# Raspberry_LCD_2023-10-31_10-21-50.net
KiCad netlist of a schematic drawn in EasyEDA Pro
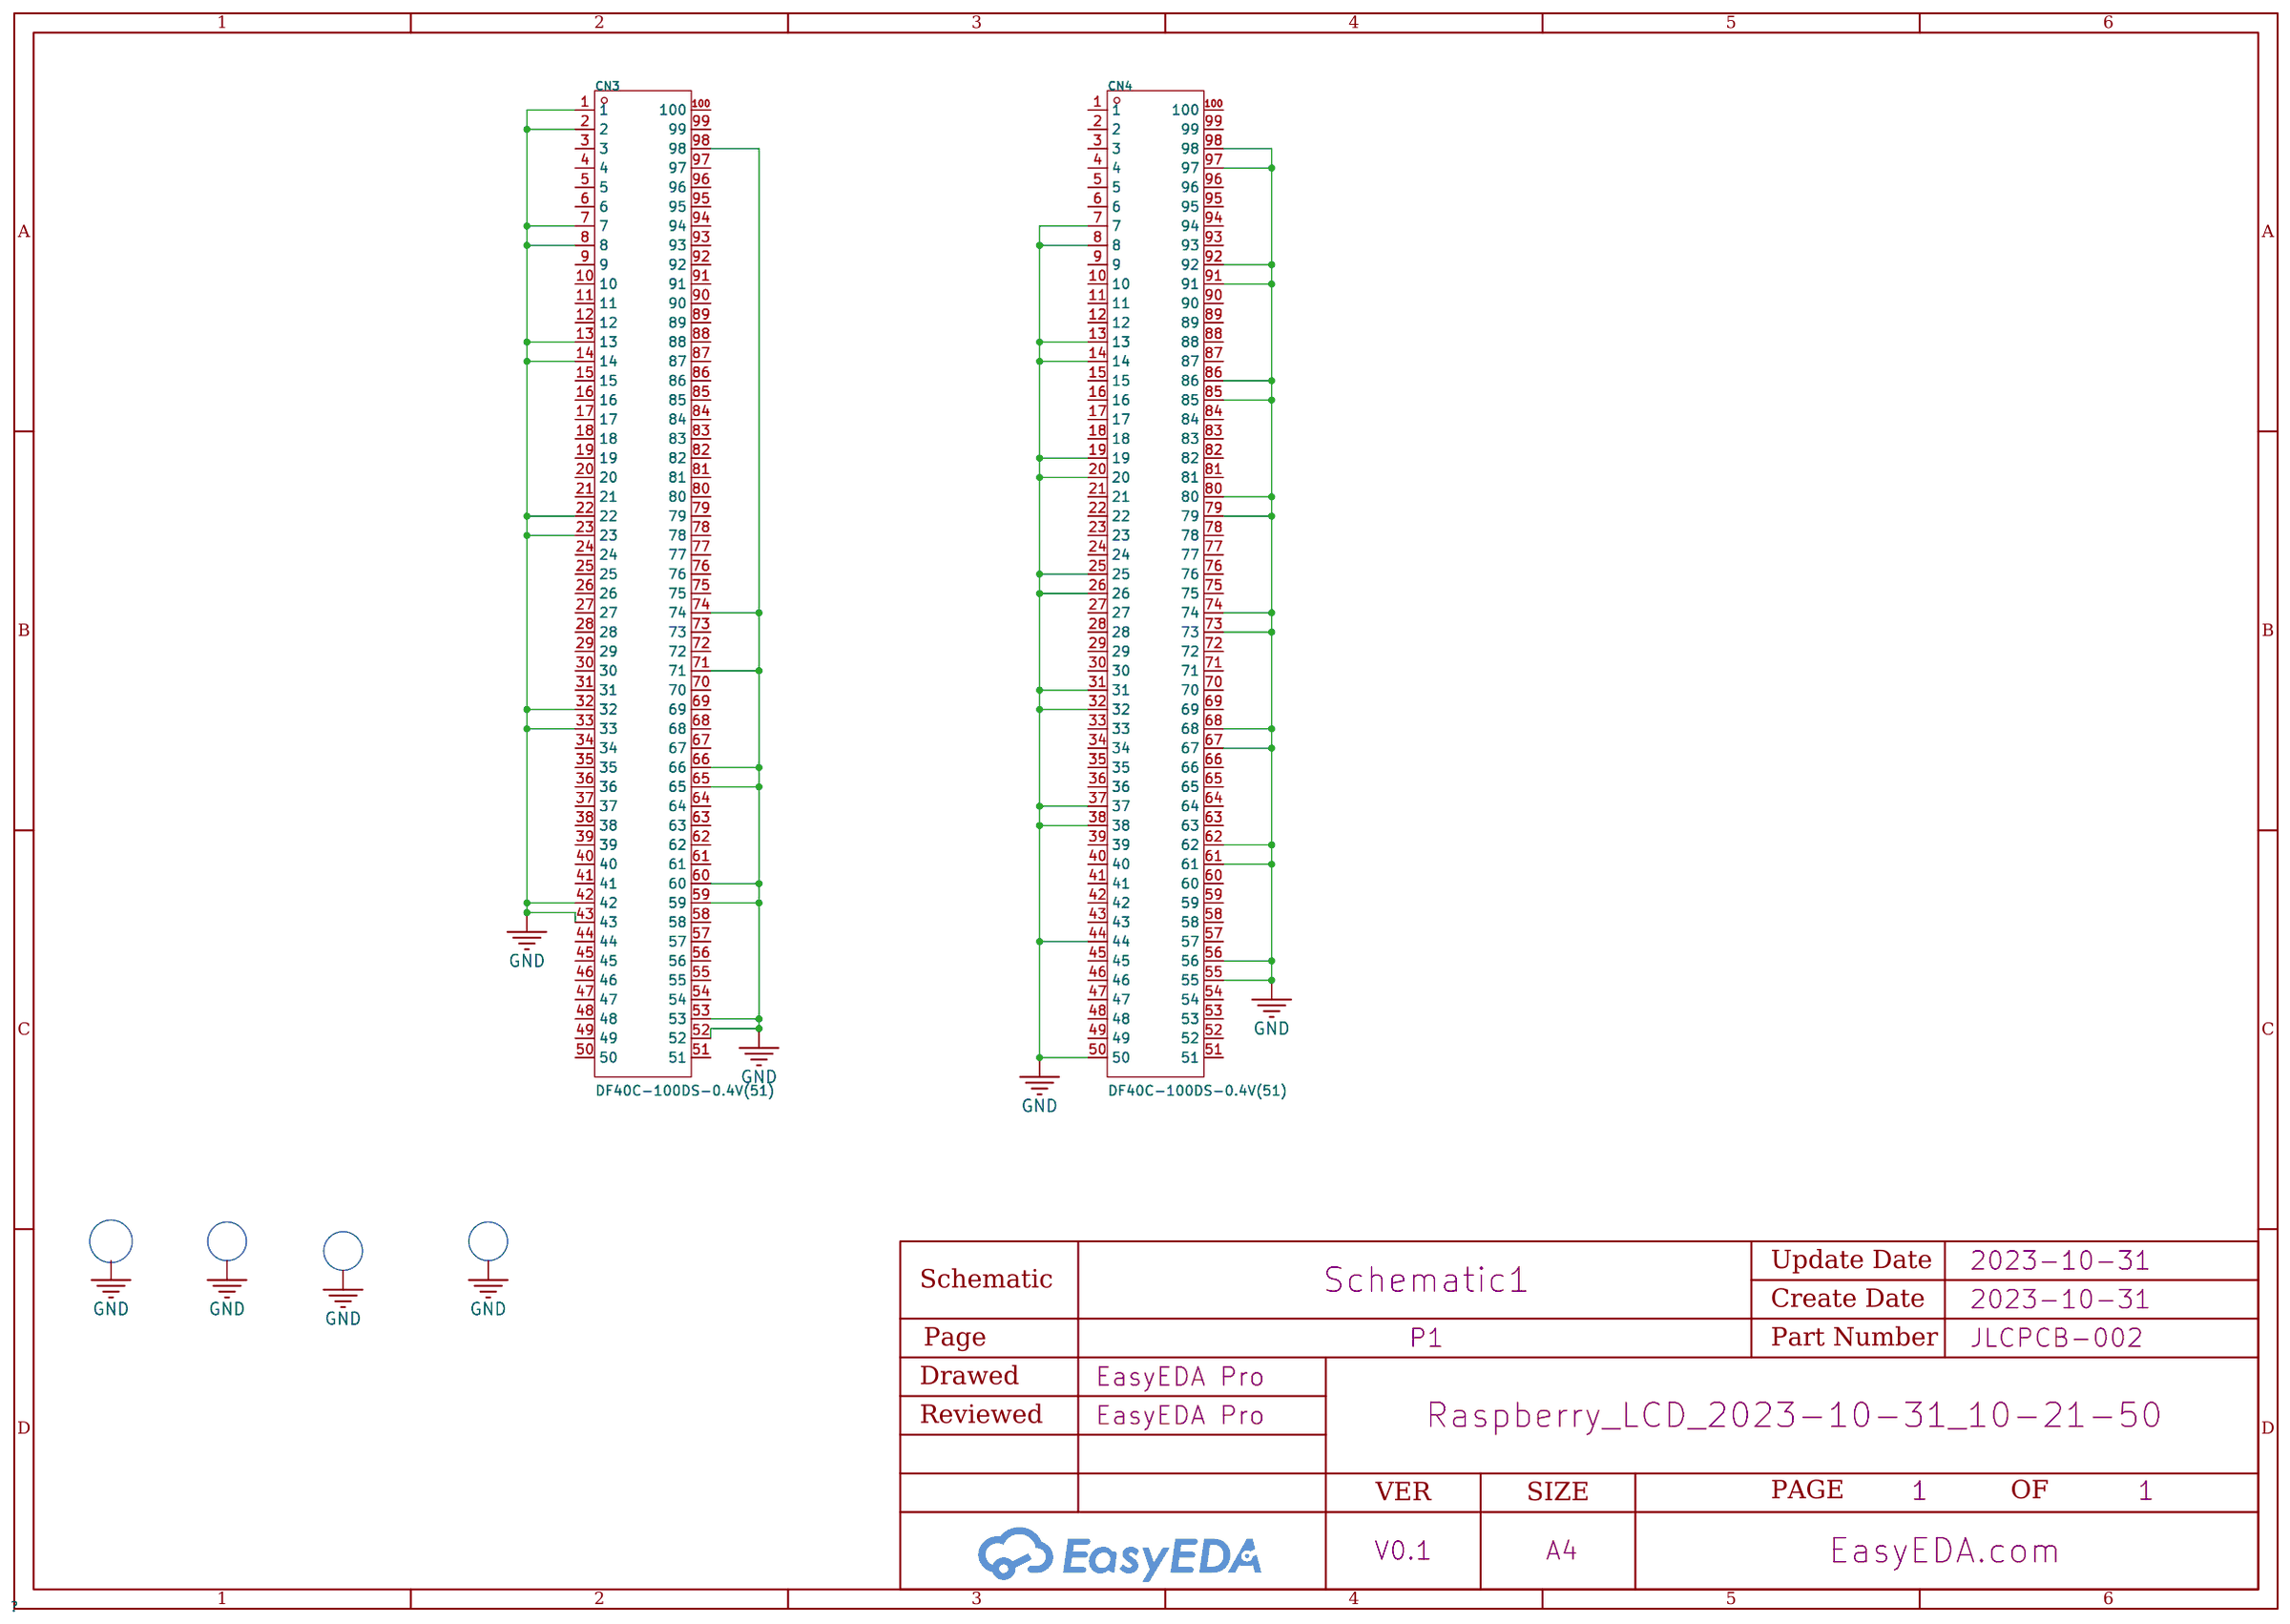
[diagram p0: schematic sheet]

(export (version "E")
  (design (tool "Eeschema 10.0.6"))
  (components
    (comp (ref "CN3")
      (value "DF40C-100DS-0.4V(51)")
      (footprint "easyedapro:CONN-SMD_DF40C-100DS-0.4V-51")
      (fields (field (name "Manufacturer") "HRS(广濑)"))
      (libsource (lib "easyedapro") (part "DF40C-100DS-0.4V(51)"))
    )
    (comp (ref "CN4")
      (value "DF40C-100DS-0.4V(51)")
      (footprint "easyedapro:CONN-SMD_DF40C-100DS-0.4V-51")
      (fields (field (name "Manufacturer") "HRS(广濑)"))
      (libsource (lib "easyedapro") (part "DF40C-100DS-0.4V(51)"))
    )
  )
  (nets
    (net (code "1") (name "GND") (class "Default")
      (node (ref "CN3") (pin "1") (pinfunction "1_1") (pintype "input"))
      (node (ref "CN3") (pin "13") (pinfunction "13_13") (pintype "input"))
      (node (ref "CN3") (pin "14") (pinfunction "14_14") (pintype "input"))
      (node (ref "CN3") (pin "2") (pinfunction "2_2") (pintype "input"))
      (node (ref "CN3") (pin "22") (pinfunction "22_22") (pintype "input"))
      (node (ref "CN3") (pin "23") (pinfunction "23_23") (pintype "input"))
      (node (ref "CN3") (pin "32") (pinfunction "32_32") (pintype "input"))
      (node (ref "CN3") (pin "33") (pinfunction "33_33") (pintype "input"))
      (node (ref "CN3") (pin "42") (pinfunction "42_42") (pintype "input"))
      (node (ref "CN3") (pin "43") (pinfunction "43_43") (pintype "input"))
      (node (ref "CN3") (pin "52") (pinfunction "52_52") (pintype "input"))
      (node (ref "CN3") (pin "53") (pinfunction "53_53") (pintype "input"))
      (node (ref "CN3") (pin "59") (pinfunction "59_59") (pintype "input"))
      (node (ref "CN3") (pin "60") (pinfunction "60_60") (pintype "input"))
      (node (ref "CN3") (pin "65") (pinfunction "65_65") (pintype "input"))
      (node (ref "CN3") (pin "66") (pinfunction "66_66") (pintype "input"))
      (node (ref "CN3") (pin "7") (pinfunction "7_7") (pintype "input"))
      (node (ref "CN3") (pin "71") (pinfunction "71_71") (pintype "input"))
      (node (ref "CN3") (pin "74") (pinfunction "74_74") (pintype "input"))
      (node (ref "CN3") (pin "8") (pinfunction "8_8") (pintype "input"))
      (node (ref "CN3") (pin "98") (pinfunction "98_98") (pintype "input"))
      (node (ref "CN4") (pin "13") (pinfunction "13_13") (pintype "input"))
      (node (ref "CN4") (pin "14") (pinfunction "14_14") (pintype "input"))
      (node (ref "CN4") (pin "19") (pinfunction "19_19") (pintype "input"))
      (node (ref "CN4") (pin "20") (pinfunction "20_20") (pintype "input"))
      (node (ref "CN4") (pin "25") (pinfunction "25_25") (pintype "input"))
      (node (ref "CN4") (pin "26") (pinfunction "26_26") (pintype "input"))
      (node (ref "CN4") (pin "31") (pinfunction "31_31") (pintype "input"))
      (node (ref "CN4") (pin "32") (pinfunction "32_32") (pintype "input"))
      (node (ref "CN4") (pin "37") (pinfunction "37_37") (pintype "input"))
      (node (ref "CN4") (pin "38") (pinfunction "38_38") (pintype "input"))
      (node (ref "CN4") (pin "44") (pinfunction "44_44") (pintype "input"))
      (node (ref "CN4") (pin "50") (pinfunction "50_50") (pintype "input"))
      (node (ref "CN4") (pin "55") (pinfunction "55_55") (pintype "input"))
      (node (ref "CN4") (pin "56") (pinfunction "56_56") (pintype "input"))
      (node (ref "CN4") (pin "61") (pinfunction "61_61") (pintype "input"))
      (node (ref "CN4") (pin "62") (pinfunction "62_62") (pintype "input"))
      (node (ref "CN4") (pin "67") (pinfunction "67_67") (pintype "input"))
      (node (ref "CN4") (pin "68") (pinfunction "68_68") (pintype "input"))
      (node (ref "CN4") (pin "7") (pinfunction "7_7") (pintype "input"))
      (node (ref "CN4") (pin "73") (pinfunction "73_73") (pintype "input"))
      (node (ref "CN4") (pin "74") (pinfunction "74_74") (pintype "input"))
      (node (ref "CN4") (pin "79") (pinfunction "79_79") (pintype "input"))
      (node (ref "CN4") (pin "8") (pinfunction "8_8") (pintype "input"))
      (node (ref "CN4") (pin "80") (pinfunction "80_80") (pintype "input"))
      (node (ref "CN4") (pin "85") (pinfunction "85_85") (pintype "input"))
      (node (ref "CN4") (pin "86") (pinfunction "86_86") (pintype "input"))
      (node (ref "CN4") (pin "91") (pinfunction "91_91") (pintype "input"))
      (node (ref "CN4") (pin "92") (pinfunction "92_92") (pintype "input"))
      (node (ref "CN4") (pin "97") (pinfunction "97_97") (pintype "input"))
      (node (ref "CN4") (pin "98") (pinfunction "98_98") (pintype "input"))
    )
    (net (code "2") (name "unconnected-(CN3-Pad3)") (class "Default")
      (node (ref "CN3") (pin "3") (pinfunction "3_3") (pintype "input"))
    )
    (net (code "3") (name "unconnected-(CN3-Pad4)") (class "Default")
      (node (ref "CN3") (pin "4") (pinfunction "4_4") (pintype "input"))
    )
    (net (code "4") (name "unconnected-(CN3-Pad5)") (class "Default")
      (node (ref "CN3") (pin "5") (pinfunction "5_5") (pintype "input"))
    )
    (net (code "5") (name "unconnected-(CN3-Pad6)") (class "Default")
      (node (ref "CN3") (pin "6") (pinfunction "6_6") (pintype "input"))
    )
    (net (code "6") (name "unconnected-(CN3-Pad9)") (class "Default")
      (node (ref "CN3") (pin "9") (pinfunction "9_9") (pintype "input"))
    )
    (net (code "7") (name "unconnected-(CN3-Pad10)") (class "Default")
      (node (ref "CN3") (pin "10") (pinfunction "10_10") (pintype "input"))
    )
    (net (code "8") (name "unconnected-(CN3-Pad11)") (class "Default")
      (node (ref "CN3") (pin "11") (pinfunction "11_11") (pintype "input"))
    )
    (net (code "9") (name "unconnected-(CN3-Pad12)") (class "Default")
      (node (ref "CN3") (pin "12") (pinfunction "12_12") (pintype "input"))
    )
    (net (code "10") (name "unconnected-(CN3-Pad15)") (class "Default")
      (node (ref "CN3") (pin "15") (pinfunction "15_15") (pintype "input"))
    )
    (net (code "11") (name "unconnected-(CN3-Pad16)") (class "Default")
      (node (ref "CN3") (pin "16") (pinfunction "16_16") (pintype "input"))
    )
    (net (code "12") (name "unconnected-(CN3-Pad17)") (class "Default")
      (node (ref "CN3") (pin "17") (pinfunction "17_17") (pintype "input"))
    )
    (net (code "13") (name "unconnected-(CN3-Pad18)") (class "Default")
      (node (ref "CN3") (pin "18") (pinfunction "18_18") (pintype "input"))
    )
    (net (code "14") (name "unconnected-(CN3-Pad19)") (class "Default")
      (node (ref "CN3") (pin "19") (pinfunction "19_19") (pintype "input"))
    )
    (net (code "15") (name "unconnected-(CN3-Pad20)") (class "Default")
      (node (ref "CN3") (pin "20") (pinfunction "20_20") (pintype "input"))
    )
    (net (code "16") (name "unconnected-(CN3-Pad21)") (class "Default")
      (node (ref "CN3") (pin "21") (pinfunction "21_21") (pintype "input"))
    )
    (net (code "17") (name "unconnected-(CN3-Pad24)") (class "Default")
      (node (ref "CN3") (pin "24") (pinfunction "24_24") (pintype "input"))
    )
    (net (code "18") (name "unconnected-(CN3-Pad25)") (class "Default")
      (node (ref "CN3") (pin "25") (pinfunction "25_25") (pintype "input"))
    )
    (net (code "19") (name "unconnected-(CN3-Pad26)") (class "Default")
      (node (ref "CN3") (pin "26") (pinfunction "26_26") (pintype "input"))
    )
    (net (code "20") (name "unconnected-(CN3-Pad27)") (class "Default")
      (node (ref "CN3") (pin "27") (pinfunction "27_27") (pintype "input"))
    )
    (net (code "21") (name "unconnected-(CN3-Pad28)") (class "Default")
      (node (ref "CN3") (pin "28") (pinfunction "28_28") (pintype "input"))
    )
    (net (code "22") (name "unconnected-(CN3-Pad29)") (class "Default")
      (node (ref "CN3") (pin "29") (pinfunction "29_29") (pintype "input"))
    )
    (net (code "23") (name "unconnected-(CN3-Pad30)") (class "Default")
      (node (ref "CN3") (pin "30") (pinfunction "30_30") (pintype "input"))
    )
    (net (code "24") (name "unconnected-(CN3-Pad31)") (class "Default")
      (node (ref "CN3") (pin "31") (pinfunction "31_31") (pintype "input"))
    )
    (net (code "25") (name "unconnected-(CN3-Pad34)") (class "Default")
      (node (ref "CN3") (pin "34") (pinfunction "34_34") (pintype "input"))
    )
    (net (code "26") (name "unconnected-(CN3-Pad35)") (class "Default")
      (node (ref "CN3") (pin "35") (pinfunction "35_35") (pintype "input"))
    )
    (net (code "27") (name "unconnected-(CN3-Pad36)") (class "Default")
      (node (ref "CN3") (pin "36") (pinfunction "36_36") (pintype "input"))
    )
    (net (code "28") (name "unconnected-(CN3-Pad37)") (class "Default")
      (node (ref "CN3") (pin "37") (pinfunction "37_37") (pintype "input"))
    )
    (net (code "29") (name "unconnected-(CN3-Pad38)") (class "Default")
      (node (ref "CN3") (pin "38") (pinfunction "38_38") (pintype "input"))
    )
    (net (code "30") (name "unconnected-(CN3-Pad39)") (class "Default")
      (node (ref "CN3") (pin "39") (pinfunction "39_39") (pintype "input"))
    )
    (net (code "31") (name "unconnected-(CN3-Pad40)") (class "Default")
      (node (ref "CN3") (pin "40") (pinfunction "40_40") (pintype "input"))
    )
    (net (code "32") (name "unconnected-(CN3-Pad41)") (class "Default")
      (node (ref "CN3") (pin "41") (pinfunction "41_41") (pintype "input"))
    )
    (net (code "33") (name "unconnected-(CN3-Pad44)") (class "Default")
      (node (ref "CN3") (pin "44") (pinfunction "44_44") (pintype "input"))
    )
    (net (code "34") (name "unconnected-(CN3-Pad45)") (class "Default")
      (node (ref "CN3") (pin "45") (pinfunction "45_45") (pintype "input"))
    )
    (net (code "35") (name "unconnected-(CN3-Pad46)") (class "Default")
      (node (ref "CN3") (pin "46") (pinfunction "46_46") (pintype "input"))
    )
    (net (code "36") (name "unconnected-(CN3-Pad47)") (class "Default")
      (node (ref "CN3") (pin "47") (pinfunction "47_47") (pintype "input"))
    )
    (net (code "37") (name "unconnected-(CN3-Pad48)") (class "Default")
      (node (ref "CN3") (pin "48") (pinfunction "48_48") (pintype "input"))
    )
    (net (code "38") (name "unconnected-(CN3-Pad49)") (class "Default")
      (node (ref "CN3") (pin "49") (pinfunction "49_49") (pintype "input"))
    )
    (net (code "39") (name "unconnected-(CN3-Pad50)") (class "Default")
      (node (ref "CN3") (pin "50") (pinfunction "50_50") (pintype "input"))
    )
    (net (code "40") (name "unconnected-(CN3-Pad51)") (class "Default")
      (node (ref "CN3") (pin "51") (pinfunction "51_51") (pintype "input"))
    )
    (net (code "41") (name "unconnected-(CN3-Pad54)") (class "Default")
      (node (ref "CN3") (pin "54") (pinfunction "54_54") (pintype "input"))
    )
    (net (code "42") (name "unconnected-(CN3-Pad55)") (class "Default")
      (node (ref "CN3") (pin "55") (pinfunction "55_55") (pintype "input"))
    )
    (net (code "43") (name "unconnected-(CN3-Pad56)") (class "Default")
      (node (ref "CN3") (pin "56") (pinfunction "56_56") (pintype "input"))
    )
    (net (code "44") (name "unconnected-(CN3-Pad57)") (class "Default")
      (node (ref "CN3") (pin "57") (pinfunction "57_57") (pintype "input"))
    )
    (net (code "45") (name "unconnected-(CN3-Pad58)") (class "Default")
      (node (ref "CN3") (pin "58") (pinfunction "58_58") (pintype "input"))
    )
    (net (code "46") (name "unconnected-(CN3-Pad61)") (class "Default")
      (node (ref "CN3") (pin "61") (pinfunction "61_61") (pintype "input"))
    )
    (net (code "47") (name "unconnected-(CN3-Pad62)") (class "Default")
      (node (ref "CN3") (pin "62") (pinfunction "62_62") (pintype "input"))
    )
    (net (code "48") (name "unconnected-(CN3-Pad63)") (class "Default")
      (node (ref "CN3") (pin "63") (pinfunction "63_63") (pintype "input"))
    )
    (net (code "49") (name "unconnected-(CN3-Pad64)") (class "Default")
      (node (ref "CN3") (pin "64") (pinfunction "64_64") (pintype "input"))
    )
    (net (code "50") (name "unconnected-(CN3-Pad67)") (class "Default")
      (node (ref "CN3") (pin "67") (pinfunction "67_67") (pintype "input"))
    )
    (net (code "51") (name "unconnected-(CN3-Pad68)") (class "Default")
      (node (ref "CN3") (pin "68") (pinfunction "68_68") (pintype "input"))
    )
    (net (code "52") (name "unconnected-(CN3-Pad69)") (class "Default")
      (node (ref "CN3") (pin "69") (pinfunction "69_69") (pintype "input"))
    )
    (net (code "53") (name "unconnected-(CN3-Pad70)") (class "Default")
      (node (ref "CN3") (pin "70") (pinfunction "70_70") (pintype "input"))
    )
    (net (code "54") (name "unconnected-(CN3-Pad72)") (class "Default")
      (node (ref "CN3") (pin "72") (pinfunction "72_72") (pintype "input"))
    )
    (net (code "55") (name "unconnected-(CN3-Pad73)") (class "Default")
      (node (ref "CN3") (pin "73") (pinfunction "73_73") (pintype "input"))
    )
    (net (code "56") (name "unconnected-(CN3-Pad75)") (class "Default")
      (node (ref "CN3") (pin "75") (pinfunction "75_75") (pintype "input"))
    )
    (net (code "57") (name "unconnected-(CN3-Pad76)") (class "Default")
      (node (ref "CN3") (pin "76") (pinfunction "76_76") (pintype "input"))
    )
    (net (code "58") (name "unconnected-(CN3-Pad77)") (class "Default")
      (node (ref "CN3") (pin "77") (pinfunction "77_77") (pintype "input"))
    )
    (net (code "59") (name "unconnected-(CN3-Pad78)") (class "Default")
      (node (ref "CN3") (pin "78") (pinfunction "78_78") (pintype "input"))
    )
    (net (code "60") (name "unconnected-(CN3-Pad79)") (class "Default")
      (node (ref "CN3") (pin "79") (pinfunction "79_79") (pintype "input"))
    )
    (net (code "61") (name "unconnected-(CN3-Pad80)") (class "Default")
      (node (ref "CN3") (pin "80") (pinfunction "80_80") (pintype "input"))
    )
    (net (code "62") (name "unconnected-(CN3-Pad81)") (class "Default")
      (node (ref "CN3") (pin "81") (pinfunction "81_81") (pintype "input"))
    )
    (net (code "63") (name "unconnected-(CN3-Pad82)") (class "Default")
      (node (ref "CN3") (pin "82") (pinfunction "82_82") (pintype "input"))
    )
    (net (code "64") (name "unconnected-(CN3-Pad83)") (class "Default")
      (node (ref "CN3") (pin "83") (pinfunction "83_83") (pintype "input"))
    )
    (net (code "65") (name "unconnected-(CN3-Pad84)") (class "Default")
      (node (ref "CN3") (pin "84") (pinfunction "84_84") (pintype "input"))
    )
    (net (code "66") (name "unconnected-(CN3-Pad85)") (class "Default")
      (node (ref "CN3") (pin "85") (pinfunction "85_85") (pintype "input"))
    )
    (net (code "67") (name "unconnected-(CN3-Pad86)") (class "Default")
      (node (ref "CN3") (pin "86") (pinfunction "86_86") (pintype "input"))
    )
    (net (code "68") (name "unconnected-(CN3-Pad87)") (class "Default")
      (node (ref "CN3") (pin "87") (pinfunction "87_87") (pintype "input"))
    )
    (net (code "69") (name "unconnected-(CN3-Pad88)") (class "Default")
      (node (ref "CN3") (pin "88") (pinfunction "88_88") (pintype "input"))
    )
    (net (code "70") (name "unconnected-(CN3-Pad89)") (class "Default")
      (node (ref "CN3") (pin "89") (pinfunction "89_89") (pintype "input"))
    )
    (net (code "71") (name "unconnected-(CN3-Pad90)") (class "Default")
      (node (ref "CN3") (pin "90") (pinfunction "90_90") (pintype "input"))
    )
    (net (code "72") (name "unconnected-(CN3-Pad91)") (class "Default")
      (node (ref "CN3") (pin "91") (pinfunction "91_91") (pintype "input"))
    )
    (net (code "73") (name "unconnected-(CN3-Pad92)") (class "Default")
      (node (ref "CN3") (pin "92") (pinfunction "92_92") (pintype "input"))
    )
    (net (code "74") (name "unconnected-(CN3-Pad93)") (class "Default")
      (node (ref "CN3") (pin "93") (pinfunction "93_93") (pintype "input"))
    )
    (net (code "75") (name "unconnected-(CN3-Pad94)") (class "Default")
      (node (ref "CN3") (pin "94") (pinfunction "94_94") (pintype "input"))
    )
    (net (code "76") (name "unconnected-(CN3-Pad95)") (class "Default")
      (node (ref "CN3") (pin "95") (pinfunction "95_95") (pintype "input"))
    )
    (net (code "77") (name "unconnected-(CN3-Pad96)") (class "Default")
      (node (ref "CN3") (pin "96") (pinfunction "96_96") (pintype "input"))
    )
    (net (code "78") (name "unconnected-(CN3-Pad97)") (class "Default")
      (node (ref "CN3") (pin "97") (pinfunction "97_97") (pintype "input"))
    )
    (net (code "79") (name "unconnected-(CN3-Pad99)") (class "Default")
      (node (ref "CN3") (pin "99") (pinfunction "99_99") (pintype "input"))
    )
    (net (code "80") (name "unconnected-(CN3-Pad100)") (class "Default")
      (node (ref "CN3") (pin "100") (pinfunction "100_100") (pintype "input"))
    )
    (net (code "81") (name "unconnected-(CN4-Pad1)") (class "Default")
      (node (ref "CN4") (pin "1") (pinfunction "1_1") (pintype "input"))
    )
    (net (code "82") (name "unconnected-(CN4-Pad2)") (class "Default")
      (node (ref "CN4") (pin "2") (pinfunction "2_2") (pintype "input"))
    )
    (net (code "83") (name "unconnected-(CN4-Pad3)") (class "Default")
      (node (ref "CN4") (pin "3") (pinfunction "3_3") (pintype "input"))
    )
    (net (code "84") (name "unconnected-(CN4-Pad4)") (class "Default")
      (node (ref "CN4") (pin "4") (pinfunction "4_4") (pintype "input"))
    )
    (net (code "85") (name "unconnected-(CN4-Pad5)") (class "Default")
      (node (ref "CN4") (pin "5") (pinfunction "5_5") (pintype "input"))
    )
    (net (code "86") (name "unconnected-(CN4-Pad6)") (class "Default")
      (node (ref "CN4") (pin "6") (pinfunction "6_6") (pintype "input"))
    )
    (net (code "87") (name "unconnected-(CN4-Pad9)") (class "Default")
      (node (ref "CN4") (pin "9") (pinfunction "9_9") (pintype "input"))
    )
    (net (code "88") (name "unconnected-(CN4-Pad10)") (class "Default")
      (node (ref "CN4") (pin "10") (pinfunction "10_10") (pintype "input"))
    )
    (net (code "89") (name "unconnected-(CN4-Pad11)") (class "Default")
      (node (ref "CN4") (pin "11") (pinfunction "11_11") (pintype "input"))
    )
    (net (code "90") (name "unconnected-(CN4-Pad12)") (class "Default")
      (node (ref "CN4") (pin "12") (pinfunction "12_12") (pintype "input"))
    )
    (net (code "91") (name "unconnected-(CN4-Pad15)") (class "Default")
      (node (ref "CN4") (pin "15") (pinfunction "15_15") (pintype "input"))
    )
    (net (code "92") (name "unconnected-(CN4-Pad16)") (class "Default")
      (node (ref "CN4") (pin "16") (pinfunction "16_16") (pintype "input"))
    )
    (net (code "93") (name "unconnected-(CN4-Pad17)") (class "Default")
      (node (ref "CN4") (pin "17") (pinfunction "17_17") (pintype "input"))
    )
    (net (code "94") (name "unconnected-(CN4-Pad18)") (class "Default")
      (node (ref "CN4") (pin "18") (pinfunction "18_18") (pintype "input"))
    )
    (net (code "95") (name "unconnected-(CN4-Pad21)") (class "Default")
      (node (ref "CN4") (pin "21") (pinfunction "21_21") (pintype "input"))
    )
    (net (code "96") (name "unconnected-(CN4-Pad22)") (class "Default")
      (node (ref "CN4") (pin "22") (pinfunction "22_22") (pintype "input"))
    )
    (net (code "97") (name "unconnected-(CN4-Pad23)") (class "Default")
      (node (ref "CN4") (pin "23") (pinfunction "23_23") (pintype "input"))
    )
    (net (code "98") (name "unconnected-(CN4-Pad24)") (class "Default")
      (node (ref "CN4") (pin "24") (pinfunction "24_24") (pintype "input"))
    )
    (net (code "99") (name "unconnected-(CN4-Pad27)") (class "Default")
      (node (ref "CN4") (pin "27") (pinfunction "27_27") (pintype "input"))
    )
    (net (code "100") (name "unconnected-(CN4-Pad28)") (class "Default")
      (node (ref "CN4") (pin "28") (pinfunction "28_28") (pintype "input"))
    )
    (net (code "101") (name "unconnected-(CN4-Pad29)") (class "Default")
      (node (ref "CN4") (pin "29") (pinfunction "29_29") (pintype "input"))
    )
    (net (code "102") (name "unconnected-(CN4-Pad30)") (class "Default")
      (node (ref "CN4") (pin "30") (pinfunction "30_30") (pintype "input"))
    )
    (net (code "103") (name "unconnected-(CN4-Pad33)") (class "Default")
      (node (ref "CN4") (pin "33") (pinfunction "33_33") (pintype "input"))
    )
    (net (code "104") (name "unconnected-(CN4-Pad34)") (class "Default")
      (node (ref "CN4") (pin "34") (pinfunction "34_34") (pintype "input"))
    )
    (net (code "105") (name "unconnected-(CN4-Pad35)") (class "Default")
      (node (ref "CN4") (pin "35") (pinfunction "35_35") (pintype "input"))
    )
    (net (code "106") (name "unconnected-(CN4-Pad36)") (class "Default")
      (node (ref "CN4") (pin "36") (pinfunction "36_36") (pintype "input"))
    )
    (net (code "107") (name "unconnected-(CN4-Pad39)") (class "Default")
      (node (ref "CN4") (pin "39") (pinfunction "39_39") (pintype "input"))
    )
    (net (code "108") (name "unconnected-(CN4-Pad40)") (class "Default")
      (node (ref "CN4") (pin "40") (pinfunction "40_40") (pintype "input"))
    )
    (net (code "109") (name "unconnected-(CN4-Pad41)") (class "Default")
      (node (ref "CN4") (pin "41") (pinfunction "41_41") (pintype "input"))
    )
    (net (code "110") (name "unconnected-(CN4-Pad42)") (class "Default")
      (node (ref "CN4") (pin "42") (pinfunction "42_42") (pintype "input"))
    )
    (net (code "111") (name "unconnected-(CN4-Pad43)") (class "Default")
      (node (ref "CN4") (pin "43") (pinfunction "43_43") (pintype "input"))
    )
    (net (code "112") (name "unconnected-(CN4-Pad45)") (class "Default")
      (node (ref "CN4") (pin "45") (pinfunction "45_45") (pintype "input"))
    )
    (net (code "113") (name "unconnected-(CN4-Pad46)") (class "Default")
      (node (ref "CN4") (pin "46") (pinfunction "46_46") (pintype "input"))
    )
    (net (code "114") (name "unconnected-(CN4-Pad47)") (class "Default")
      (node (ref "CN4") (pin "47") (pinfunction "47_47") (pintype "input"))
    )
    (net (code "115") (name "unconnected-(CN4-Pad48)") (class "Default")
      (node (ref "CN4") (pin "48") (pinfunction "48_48") (pintype "input"))
    )
    (net (code "116") (name "unconnected-(CN4-Pad49)") (class "Default")
      (node (ref "CN4") (pin "49") (pinfunction "49_49") (pintype "input"))
    )
    (net (code "117") (name "unconnected-(CN4-Pad51)") (class "Default")
      (node (ref "CN4") (pin "51") (pinfunction "51_51") (pintype "input"))
    )
    (net (code "118") (name "unconnected-(CN4-Pad52)") (class "Default")
      (node (ref "CN4") (pin "52") (pinfunction "52_52") (pintype "input"))
    )
    (net (code "119") (name "unconnected-(CN4-Pad53)") (class "Default")
      (node (ref "CN4") (pin "53") (pinfunction "53_53") (pintype "input"))
    )
    (net (code "120") (name "unconnected-(CN4-Pad54)") (class "Default")
      (node (ref "CN4") (pin "54") (pinfunction "54_54") (pintype "input"))
    )
    (net (code "121") (name "unconnected-(CN4-Pad57)") (class "Default")
      (node (ref "CN4") (pin "57") (pinfunction "57_57") (pintype "input"))
    )
    (net (code "122") (name "unconnected-(CN4-Pad58)") (class "Default")
      (node (ref "CN4") (pin "58") (pinfunction "58_58") (pintype "input"))
    )
    (net (code "123") (name "unconnected-(CN4-Pad59)") (class "Default")
      (node (ref "CN4") (pin "59") (pinfunction "59_59") (pintype "input"))
    )
    (net (code "124") (name "unconnected-(CN4-Pad60)") (class "Default")
      (node (ref "CN4") (pin "60") (pinfunction "60_60") (pintype "input"))
    )
    (net (code "125") (name "unconnected-(CN4-Pad63)") (class "Default")
      (node (ref "CN4") (pin "63") (pinfunction "63_63") (pintype "input"))
    )
    (net (code "126") (name "unconnected-(CN4-Pad64)") (class "Default")
      (node (ref "CN4") (pin "64") (pinfunction "64_64") (pintype "input"))
    )
    (net (code "127") (name "unconnected-(CN4-Pad65)") (class "Default")
      (node (ref "CN4") (pin "65") (pinfunction "65_65") (pintype "input"))
    )
    (net (code "128") (name "unconnected-(CN4-Pad66)") (class "Default")
      (node (ref "CN4") (pin "66") (pinfunction "66_66") (pintype "input"))
    )
    (net (code "129") (name "unconnected-(CN4-Pad69)") (class "Default")
      (node (ref "CN4") (pin "69") (pinfunction "69_69") (pintype "input"))
    )
    (net (code "130") (name "unconnected-(CN4-Pad70)") (class "Default")
      (node (ref "CN4") (pin "70") (pinfunction "70_70") (pintype "input"))
    )
    (net (code "131") (name "unconnected-(CN4-Pad71)") (class "Default")
      (node (ref "CN4") (pin "71") (pinfunction "71_71") (pintype "input"))
    )
    (net (code "132") (name "unconnected-(CN4-Pad72)") (class "Default")
      (node (ref "CN4") (pin "72") (pinfunction "72_72") (pintype "input"))
    )
    (net (code "133") (name "unconnected-(CN4-Pad75)") (class "Default")
      (node (ref "CN4") (pin "75") (pinfunction "75_75") (pintype "input"))
    )
    (net (code "134") (name "unconnected-(CN4-Pad76)") (class "Default")
      (node (ref "CN4") (pin "76") (pinfunction "76_76") (pintype "input"))
    )
    (net (code "135") (name "unconnected-(CN4-Pad77)") (class "Default")
      (node (ref "CN4") (pin "77") (pinfunction "77_77") (pintype "input"))
    )
    (net (code "136") (name "unconnected-(CN4-Pad78)") (class "Default")
      (node (ref "CN4") (pin "78") (pinfunction "78_78") (pintype "input"))
    )
    (net (code "137") (name "unconnected-(CN4-Pad81)") (class "Default")
      (node (ref "CN4") (pin "81") (pinfunction "81_81") (pintype "input"))
    )
    (net (code "138") (name "unconnected-(CN4-Pad82)") (class "Default")
      (node (ref "CN4") (pin "82") (pinfunction "82_82") (pintype "input"))
    )
    (net (code "139") (name "unconnected-(CN4-Pad83)") (class "Default")
      (node (ref "CN4") (pin "83") (pinfunction "83_83") (pintype "input"))
    )
    (net (code "140") (name "unconnected-(CN4-Pad84)") (class "Default")
      (node (ref "CN4") (pin "84") (pinfunction "84_84") (pintype "input"))
    )
    (net (code "141") (name "unconnected-(CN4-Pad87)") (class "Default")
      (node (ref "CN4") (pin "87") (pinfunction "87_87") (pintype "input"))
    )
    (net (code "142") (name "unconnected-(CN4-Pad88)") (class "Default")
      (node (ref "CN4") (pin "88") (pinfunction "88_88") (pintype "input"))
    )
    (net (code "143") (name "unconnected-(CN4-Pad89)") (class "Default")
      (node (ref "CN4") (pin "89") (pinfunction "89_89") (pintype "input"))
    )
    (net (code "144") (name "unconnected-(CN4-Pad90)") (class "Default")
      (node (ref "CN4") (pin "90") (pinfunction "90_90") (pintype "input"))
    )
    (net (code "145") (name "unconnected-(CN4-Pad93)") (class "Default")
      (node (ref "CN4") (pin "93") (pinfunction "93_93") (pintype "input"))
    )
    (net (code "146") (name "unconnected-(CN4-Pad94)") (class "Default")
      (node (ref "CN4") (pin "94") (pinfunction "94_94") (pintype "input"))
    )
    (net (code "147") (name "unconnected-(CN4-Pad95)") (class "Default")
      (node (ref "CN4") (pin "95") (pinfunction "95_95") (pintype "input"))
    )
    (net (code "148") (name "unconnected-(CN4-Pad96)") (class "Default")
      (node (ref "CN4") (pin "96") (pinfunction "96_96") (pintype "input"))
    )
    (net (code "149") (name "unconnected-(CN4-Pad99)") (class "Default")
      (node (ref "CN4") (pin "99") (pinfunction "99_99") (pintype "input"))
    )
    (net (code "150") (name "unconnected-(CN4-Pad100)") (class "Default")
      (node (ref "CN4") (pin "100") (pinfunction "100_100") (pintype "input"))
    )
  )
)
